# Supply.net
KiCad netlist of a schematic drawn in Altium Designer
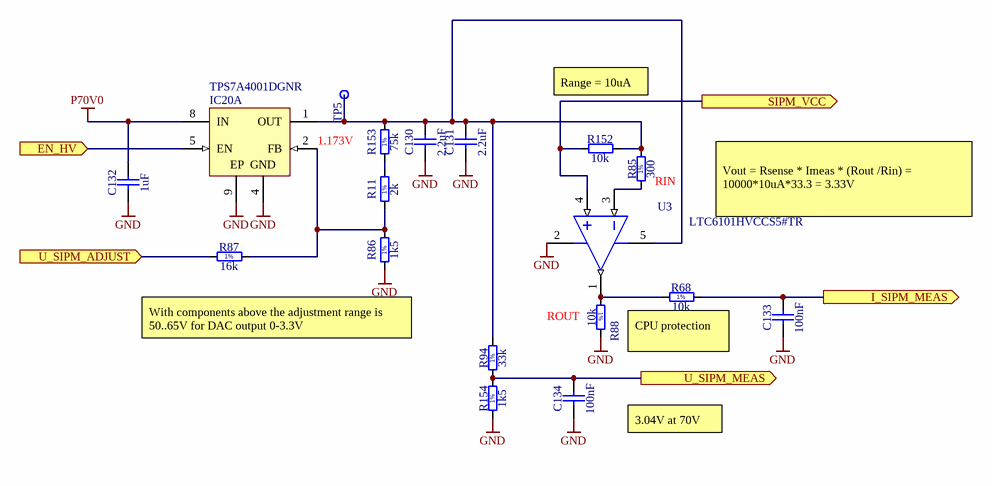
[diagram p0: Supply.SchDoc]

(export (version "E")
  (design (tool "Eeschema 10.0.6"))
  (components
    (comp (ref "C130")
      (value "2.2uF")
      (footprint "CAPC3225X230N")
      (description "Non-polarised capacitor")
      (fields
        (field (name "PART NUMBER") "CC1210_2.2UF_100V_10%_X7R_MURATA_GCJ32DR72A225KA01L")
        (field (name "VOLTAGE") "100V")
        (field (name "AUTHOR") "CERN DEM JLC")
      )
      (libsource (lib "Capacitors") (part "Capacitor - non polarized"))
    )
    (comp (ref "C131")
      (value "2.2uF")
      (footprint "CAPC3225X230N")
      (description "Non-polarised capacitor")
      (fields
        (field (name "PART NUMBER") "CC1210_2.2UF_100V_10%_X7R_MURATA_GCJ32DR72A225KA01L")
        (field (name "VOLTAGE") "100V")
        (field (name "AUTHOR") "CERN DEM JLC")
      )
      (libsource (lib "Capacitors") (part "Capacitor - non polarized"))
    )
    (comp (ref "C132")
      (value "1uF")
      (footprint "CAPC2013X145N")
      (description "Non-polarised capacitor")
      (fields
        (field (name "PART NUMBER") "CC0805_1UF_100V_10%_X7S")
        (field (name "VOLTAGE") "100V")
        (field (name "AUTHOR") "CERN DEM JLC")
      )
      (libsource (lib "Capacitors") (part "Capacitor - non polarized"))
    )
    (comp (ref "C133")
      (value "100nF")
      (footprint "CAPC1005X55N")
      (description "Non-polarised capacitor")
      (fields
        (field (name "PART NUMBER") "CC0402_100NF_16V_10%_X7R")
        (field (name "VOLTAGE") "16V")
        (field (name "AUTHOR") "CERN DEM JLC")
      )
      (libsource (lib "Capacitors") (part "Capacitor - non polarized"))
    )
    (comp (ref "C134")
      (value "100nF")
      (footprint "CAPC1005X55N")
      (description "Non-polarised capacitor")
      (fields
        (field (name "PART NUMBER") "CC0402_100NF_16V_10%_X7R")
        (field (name "VOLTAGE") "16V")
        (field (name "AUTHOR") "CERN DEM JLC")
      )
      (libsource (lib "Capacitors") (part "Capacitor - non polarized"))
    )
    (comp (ref "IC20")
      (value "TPS7A4001DGNR")
      (footprint "DGN0008B_M")
      (fields (field (name "MANUFACTURER") "Texas Instruments"))
      (libsource (lib "Altium Content Vault") (part "TI-TPS7A4X01DGN8-1880X1750TP"))
    )
    (comp (ref "R11")
      (value "2k")
      (footprint "RESC1005X40N")
      (description "Resistor - 1%")
      (fields
        (field (name "PART NUMBER") "R0402_2K_1%_0.0625W_100PPM")
        (field (name "POWER") "0.0625W")
        (field (name "AUTHOR") "CERN DEM JLC")
      )
      (libsource (lib "Resistors") (part "Resistor - 1%"))
    )
    (comp (ref "R68")
      (value "10k")
      (footprint "RESC1005X40N")
      (description "Resistor - 1%")
      (fields
        (field (name "PART NUMBER") "R0402_10K_1%_0.0625W_100PPM")
        (field (name "POWER") "0.0625W")
        (field (name "AUTHOR") "CERN DEM JLC")
      )
      (libsource (lib "Resistors") (part "Resistor - 1%"))
    )
    (comp (ref "R85")
      (value "300")
      (footprint "RESC1005X40N")
      (description "Resistor - 1%")
      (fields
        (field (name "PART NUMBER") "R0402_300R_1%_0.0625W_100PPM")
        (field (name "POWER") "0.0625W")
        (field (name "AUTHOR") "CERN DEM JLC")
      )
      (libsource (lib "Resistors") (part "Resistor - 1%"))
    )
    (comp (ref "R86")
      (value "1k5")
      (footprint "RESC1005X40N")
      (description "Resistor - 1%")
      (fields
        (field (name "PART NUMBER") "R0402_1K5_1%_0.0625W_100PPM")
        (field (name "POWER") "0.0625W")
        (field (name "AUTHOR") "CERN DEM JLC")
      )
      (libsource (lib "Resistors") (part "Resistor - 1%"))
    )
    (comp (ref "R87")
      (value "16k")
      (footprint "RESC1005X40N")
      (description "Resistor - 1%")
      (fields
        (field (name "PART NUMBER") "R0402_16K_1%_0.0625W_100PPM")
        (field (name "POWER") "0.0625W")
        (field (name "AUTHOR") "CERN DEM JLC")
      )
      (libsource (lib "Resistors") (part "Resistor - 1%"))
    )
    (comp (ref "R88")
      (value "10k")
      (footprint "RESC1005X40N")
      (description "Resistor - 1%")
      (fields
        (field (name "PART NUMBER") "R0402_10K_1%_0.0625W_100PPM")
        (field (name "POWER") "0.0625W")
        (field (name "AUTHOR") "CERN DEM JLC")
      )
      (libsource (lib "Resistors") (part "Resistor - 1%"))
    )
    (comp (ref "R94")
      (value "33k")
      (footprint "RESC2012X60N")
      (description "Resistor - 1%")
      (fields
        (field (name "PART NUMBER") "R0805_33K_1%_0.125W_100PPM")
        (field (name "POWER") "0.125W")
        (field (name "AUTHOR") "CERN DEM JLC")
      )
      (libsource (lib "Resistors") (part "Resistor - 1%"))
    )
    (comp (ref "R152")
      (value "10k")
      (footprint "RESC1608X55N")
      (description "Resistor - 1%")
      (fields
        (field (name "PART NUMBER") "R0603_10K_1%_0.1W_100PPM")
        (field (name "POWER") "0.1W")
        (field (name "AUTHOR") "CERN DEM JLC")
      )
      (libsource (lib "") (part "Resistor - 1%_1"))
    )
    (comp (ref "R153")
      (value "75k")
      (footprint "RESC1608X55N")
      (description "Resistor - 1%")
      (fields
        (field (name "PART NUMBER") "R0603_75K_1%_0.1W_100PPM")
        (field (name "POWER") "0.1W")
        (field (name "AUTHOR") "CERN DEM JLC")
      )
      (libsource (lib "Resistors") (part "Resistor - 1%"))
    )
    (comp (ref "R154")
      (value "1k5")
      (footprint "RESC1005X40N")
      (description "Resistor - 1%")
      (fields
        (field (name "PART NUMBER") "R0402_1K5_1%_0.0625W_100PPM")
        (field (name "POWER") "0.0625W")
        (field (name "AUTHOR") "CERN DEM JLC")
      )
      (libsource (lib "Resistors") (part "Resistor - 1%"))
    )
    (comp (ref "TP5")
      (value "Test Point")
      (footprint "TPS127")
      (fields (field (name "PART NUMBER") "SMD_PAD_1.27X1.27MM") (field (name "AUTHOR") "CERN DEM JLC"))
      (libsource (lib "Eletro-mechanical") (part "Test Point"))
    )
    (comp (ref "U3")
      (value "LTC6101HVCCS5#TR")
      (footprint "LT-S5-5-TSOT-23_M")
      (fields
        (field (name "LINEAR TECHNOLOGY PART NUMBER") "LTC6101HV")
        (field (name "MANUFACTURER") "Linear Technology")
      )
      (libsource (lib "Altium Content Vault") (part "LT-LT6106-LTC6101HV-5"))
    )
  )
  (nets
    (net (code "1") (name "/EN_HV") (class "Default")
      (node (ref "IC20") (pin "5") (pinfunction "EN_5") (pintype "input"))
    )
    (net (code "2") (name "/I_SIPM_MEAS") (class "Default")
      (node (ref "C133") (pin "2") (pinfunction "2_2") (pintype "passive"))
      (node (ref "R68") (pin "2") (pinfunction "2_2") (pintype "passive"))
    )
    (net (code "3") (name "/SIPM_VCC") (class "Default")
      (node (ref "R152") (pin "1") (pinfunction "1_1") (pintype "passive"))
      (node (ref "U3") (pin "4") (pinfunction "+IN_4") (pintype "input"))
    )
    (net (code "4") (name "/U_SIPM_ADJUST") (class "Default")
      (node (ref "R87") (pin "1") (pinfunction "1_1") (pintype "passive"))
    )
    (net (code "5") (name "/U_SIPM_MEAS") (class "Default")
      (node (ref "C134") (pin "2") (pinfunction "2_2") (pintype "passive"))
      (node (ref "R154") (pin "2") (pinfunction "2_2") (pintype "passive"))
      (node (ref "R94") (pin "1") (pinfunction "1_1") (pintype "passive"))
    )
    (net (code "6") (name "GND") (class "Default")
      (node (ref "C130") (pin "1") (pinfunction "1_1") (pintype "passive"))
      (node (ref "C131") (pin "1") (pinfunction "1_1") (pintype "passive"))
      (node (ref "C132") (pin "1") (pinfunction "1_1") (pintype "passive"))
      (node (ref "C133") (pin "1") (pinfunction "1_1") (pintype "passive"))
      (node (ref "C134") (pin "1") (pinfunction "1_1") (pintype "passive"))
      (node (ref "IC20") (pin "4") (pinfunction "GND_4") (pintype "power_in"))
      (node (ref "IC20") (pin "9") (pinfunction "EP_9") (pintype "power_in"))
      (node (ref "R154") (pin "1") (pinfunction "1_1") (pintype "passive"))
      (node (ref "R86") (pin "1") (pinfunction "1_1") (pintype "passive"))
      (node (ref "R88") (pin "2") (pinfunction "2_2") (pintype "passive"))
      (node (ref "U3") (pin "2") (pinfunction "V-_2") (pintype "power_in"))
    )
    (net (code "7") (name "Net-(IC20A-FB)") (class "Default")
      (node (ref "IC20") (pin "2") (pinfunction "FB_2") (pintype "input"))
      (node (ref "R11") (pin "1") (pinfunction "1_1") (pintype "passive"))
      (node (ref "R86") (pin "2") (pinfunction "2_2") (pintype "passive"))
      (node (ref "R87") (pin "2") (pinfunction "2_2") (pintype "passive"))
    )
    (net (code "8") (name "Net-(IC20A-OUT)") (class "Default")
      (node (ref "C130") (pin "2") (pinfunction "2_2") (pintype "passive"))
      (node (ref "C131") (pin "2") (pinfunction "2_2") (pintype "passive"))
      (node (ref "IC20") (pin "1") (pinfunction "OUT_1") (pintype "power_in"))
      (node (ref "R152") (pin "2") (pinfunction "2_2") (pintype "passive"))
      (node (ref "R153") (pin "2") (pinfunction "2_2") (pintype "passive"))
      (node (ref "R85") (pin "2") (pinfunction "2_2") (pintype "passive"))
      (node (ref "R94") (pin "2") (pinfunction "2_2") (pintype "passive"))
      (node (ref "TP5") (pin "1") (pinfunction "1_1") (pintype "bidirectional"))
      (node (ref "U3") (pin "5") (pinfunction "V+_5") (pintype "power_in"))
    )
    (net (code "9") (name "Net-(R11-Pad2)") (class "Default")
      (node (ref "R11") (pin "2") (pinfunction "2_2") (pintype "passive"))
      (node (ref "R153") (pin "1") (pinfunction "1_1") (pintype "passive"))
    )
    (net (code "10") (name "Net-(U3--IN)") (class "Default")
      (node (ref "R85") (pin "1") (pinfunction "1_1") (pintype "passive"))
      (node (ref "U3") (pin "3") (pinfunction "-IN_3") (pintype "input"))
    )
    (net (code "11") (name "Net-(U3-OUT)") (class "Default")
      (node (ref "R68") (pin "1") (pinfunction "1_1") (pintype "passive"))
      (node (ref "R88") (pin "1") (pinfunction "1_1") (pintype "passive"))
      (node (ref "U3") (pin "1") (pinfunction "OUT_1") (pintype "output"))
    )
    (net (code "12") (name "P70V0") (class "Default")
      (node (ref "C132") (pin "2") (pinfunction "2_2") (pintype "passive"))
      (node (ref "IC20") (pin "8") (pinfunction "IN_8") (pintype "power_in"))
    )
  )
)
